# push.net
KiCad netlist of a schematic drawn in EAGLE
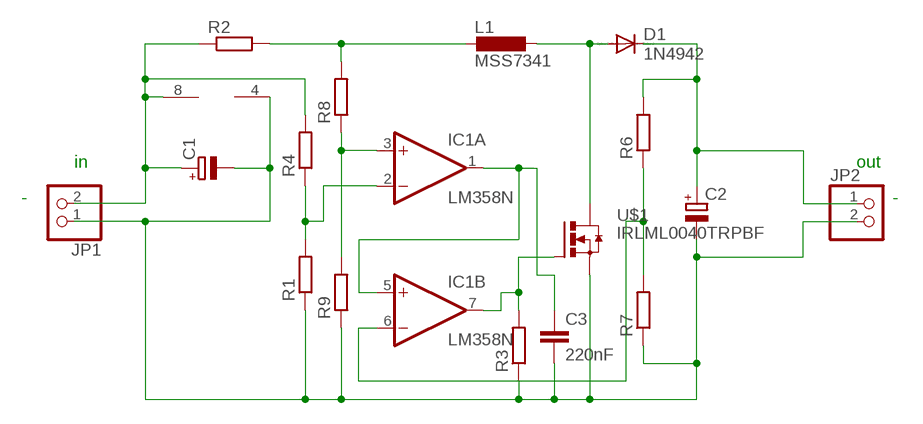
[diagram p0: schematic, sheet 1]

(export (version "E")
  (design (tool "Eeschema 10.0.6"))
  (components
    (comp (ref "C1")
      (value "CPOL-EUE3.5-8")
      (footprint "eagle-import:E3,5-8")
      (libsource (lib "eagle-import") (part "CPOL-EUE3.5-8"))
    )
    (comp (ref "C2")
      (value "CPOL-EUE3.5-8")
      (footprint "eagle-import:E3,5-8")
      (libsource (lib "eagle-import") (part "CPOL-EUE3.5-8"))
    )
    (comp (ref "C3")
      (value "220nF")
      (footprint "eagle-import:C1206")
      (libsource (lib "eagle-import") (part "C-EUC1206"))
    )
    (comp (ref "D1")
      (value "1N4942")
      (footprint "eagle-import:DO41-10")
      (libsource (lib "eagle-import") (part "1N4942"))
    )
    (comp (ref "IC1")
      (value "LM358N")
      (footprint "eagle-import:DIL08")
      (libsource (lib "eagle-import") (part "LM358N"))
    )
    (comp (ref "JP1")
      (value "PINHD-1X2")
      (footprint "eagle-import:1X02")
      (libsource (lib "eagle-import") (part "PINHD-1X2"))
    )
    (comp (ref "JP2")
      (value "PINHD-1X2")
      (footprint "eagle-import:1X02")
      (libsource (lib "eagle-import") (part "PINHD-1X2"))
    )
    (comp (ref "L1")
      (value "MSS7341")
      (footprint "eagle-import:MSS7341")
      (libsource (lib "eagle-import") (part "MSS7341"))
    )
    (comp (ref "R1")
      (value "R-EU_R1206")
      (footprint "eagle-import:R1206")
      (libsource (lib "eagle-import") (part "R-EU_R1206"))
    )
    (comp (ref "R2")
      (value "R-EU_R1206")
      (footprint "eagle-import:R1206")
      (libsource (lib "eagle-import") (part "R-EU_R1206"))
    )
    (comp (ref "R3")
      (value "R-EU_R1206")
      (footprint "eagle-import:R1206")
      (libsource (lib "eagle-import") (part "R-EU_R1206"))
    )
    (comp (ref "R4")
      (value "R-EU_R1206")
      (footprint "eagle-import:R1206")
      (libsource (lib "eagle-import") (part "R-EU_R1206"))
    )
    (comp (ref "R6")
      (value "R-EU_R1206")
      (footprint "eagle-import:R1206")
      (libsource (lib "eagle-import") (part "R-EU_R1206"))
    )
    (comp (ref "R7")
      (value "R-EU_R1206")
      (footprint "eagle-import:R1206")
      (libsource (lib "eagle-import") (part "R-EU_R1206"))
    )
    (comp (ref "R8")
      (value "R-EU_R1206")
      (footprint "eagle-import:R1206")
      (libsource (lib "eagle-import") (part "R-EU_R1206"))
    )
    (comp (ref "R9")
      (value "R-EU_R1206")
      (footprint "eagle-import:R1206")
      (libsource (lib "eagle-import") (part "R-EU_R1206"))
    )
    (comp (ref "U$1")
      (value "IRLML0040TRPBF")
      (footprint "eagle-import:MICRO3")
      (libsource (lib "eagle-import") (part "IRLML0040TRPBF"))
    )
  )
  (nets
    (net (code "1") (name "Net-(C2-Pad+)") (class "Default")
      (node (ref "C2") (pin "+") (pinfunction "+_+") (pintype "passive"))
      (node (ref "D1") (pin "C") (pinfunction "C_C") (pintype "passive"))
      (node (ref "JP2") (pin "1") (pinfunction "1_1") (pintype "passive"))
      (node (ref "R6") (pin "2") (pinfunction "2_2") (pintype "passive"))
    )
    (net (code "2") (name "Net-(IC1A-+IN)") (class "Default")
      (node (ref "IC1") (pin "3") (pinfunction "+IN_3") (pintype "input"))
      (node (ref "R8") (pin "1") (pinfunction "1_1") (pintype "passive"))
      (node (ref "R9") (pin "2") (pinfunction "2_2") (pintype "passive"))
    )
    (net (code "3") (name "Net-(IC1A--IN)") (class "Default")
      (node (ref "IC1") (pin "2") (pinfunction "-IN_2") (pintype "input"))
      (node (ref "R1") (pin "2") (pinfunction "2_2") (pintype "passive"))
      (node (ref "R4") (pin "1") (pinfunction "1_1") (pintype "passive"))
    )
    (net (code "4") (name "Net-(IC1A-OUT)") (class "Default")
      (node (ref "C3") (pin "1") (pinfunction "1_1") (pintype "passive"))
      (node (ref "IC1") (pin "1") (pinfunction "OUT_1") (pintype "output"))
      (node (ref "IC1") (pin "5") (pinfunction "+IN_5") (pintype "input"))
    )
    (net (code "5") (name "Net-(IC1B--IN)") (class "Default")
      (node (ref "IC1") (pin "6") (pinfunction "-IN_6") (pintype "input"))
      (node (ref "R6") (pin "1") (pinfunction "1_1") (pintype "passive"))
      (node (ref "R7") (pin "2") (pinfunction "2_2") (pintype "passive"))
    )
    (net (code "6") (name "Net-(IC1B-OUT)") (class "Default")
      (node (ref "IC1") (pin "7") (pinfunction "OUT_7") (pintype "output"))
      (node (ref "R3") (pin "2") (pinfunction "2_2") (pintype "passive"))
      (node (ref "U$1") (pin "1") (pinfunction "G_1") (pintype "passive"))
    )
    (net (code "7") (name "Net-(IC1C-V+)") (class "Default")
      (node (ref "C1") (pin "+") (pinfunction "+_+") (pintype "passive"))
      (node (ref "IC1") (pin "8") (pinfunction "V+_8") (pintype "power_in"))
      (node (ref "JP1") (pin "2") (pinfunction "2_2") (pintype "passive"))
      (node (ref "R2") (pin "1") (pinfunction "1_1") (pintype "passive"))
      (node (ref "R4") (pin "2") (pinfunction "2_2") (pintype "passive"))
    )
    (net (code "8") (name "Net-(IC1C-V-)") (class "Default")
      (node (ref "C1") (pin "-") (pinfunction "-_-") (pintype "passive"))
      (node (ref "C2") (pin "-") (pinfunction "-_-") (pintype "passive"))
      (node (ref "C3") (pin "2") (pinfunction "2_2") (pintype "passive"))
      (node (ref "IC1") (pin "4") (pinfunction "V-_4") (pintype "power_in"))
      (node (ref "JP1") (pin "1") (pinfunction "1_1") (pintype "passive"))
      (node (ref "JP2") (pin "2") (pinfunction "2_2") (pintype "passive"))
      (node (ref "R1") (pin "1") (pinfunction "1_1") (pintype "passive"))
      (node (ref "R3") (pin "1") (pinfunction "1_1") (pintype "passive"))
      (node (ref "R7") (pin "1") (pinfunction "1_1") (pintype "passive"))
      (node (ref "R9") (pin "1") (pinfunction "1_1") (pintype "passive"))
      (node (ref "U$1") (pin "2") (pinfunction "S_2") (pintype "passive"))
    )
    (net (code "9") (name "Net-(L1-Pad1)") (class "Default")
      (node (ref "L1") (pin "1") (pinfunction "1_1") (pintype "passive"))
      (node (ref "R2") (pin "2") (pinfunction "2_2") (pintype "passive"))
      (node (ref "R8") (pin "2") (pinfunction "2_2") (pintype "passive"))
    )
    (net (code "10") (name "Net-(U$1-D)") (class "Default")
      (node (ref "D1") (pin "A") (pinfunction "A_A") (pintype "passive"))
      (node (ref "L1") (pin "2") (pinfunction "2_2") (pintype "passive"))
      (node (ref "U$1") (pin "3") (pinfunction "D_3") (pintype "passive"))
    )
  )
)
